# working.net
KiCad netlist of a schematic drawn in EAGLE
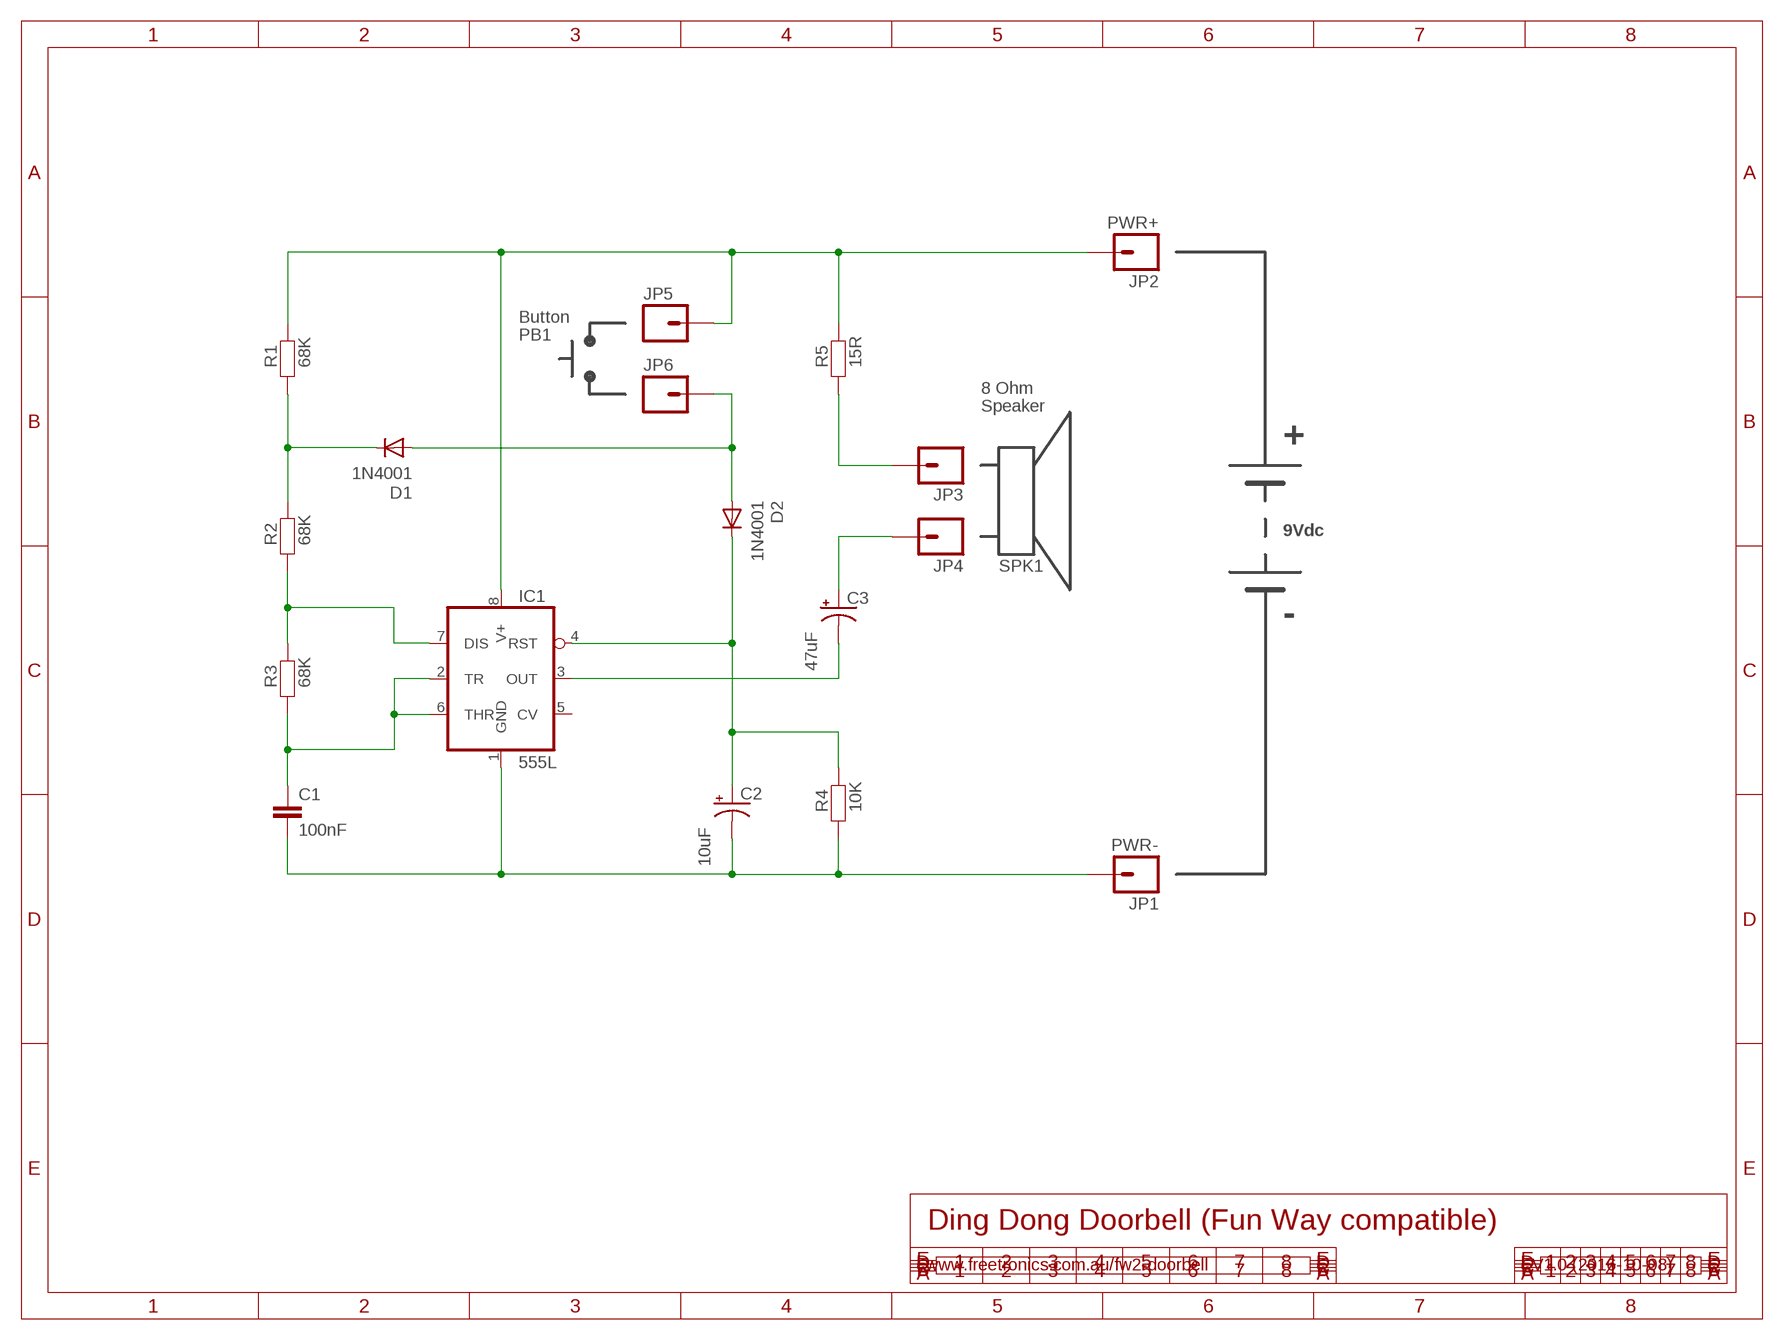
[diagram p0: schematic, sheet 1]

(export (version "E")
  (design (tool "Eeschema 10.0.6"))
  (components
    (comp (ref "C1")
      (value "100nF")
      (footprint "eagle-import:CAP-PTH-SMALL")
      (libsource (lib "eagle-import") (part "CAPPTH"))
    )
    (comp (ref "C2")
      (value "10uF")
      (footprint "eagle-import:CPOL-RADIAL-10UF-25V")
      (libsource (lib "eagle-import") (part "CAP_POLPTH2"))
    )
    (comp (ref "C3")
      (value "47uF")
      (footprint "eagle-import:CPOL-RADIAL-10UF-25V")
      (libsource (lib "eagle-import") (part "CAP_POLPTH2"))
    )
    (comp (ref "D1")
      (value "1N4001")
      (footprint "eagle-import:DIODE-1N4001")
      (libsource (lib "eagle-import") (part "DIODEPTH"))
    )
    (comp (ref "D2")
      (value "1N4001")
      (footprint "eagle-import:DIODE-1N4001")
      (libsource (lib "eagle-import") (part "DIODEPTH"))
    )
    (comp (ref "IC1")
      (value "555L")
      (footprint "eagle-import:DIL08L")
      (libsource (lib "eagle-import") (part "555L"))
    )
    (comp (ref "JP1")
      (value "PWR-")
      (footprint "eagle-import:1X01")
      (libsource (lib "eagle-import") (part "M01PTH"))
    )
    (comp (ref "JP2")
      (value "PWR+")
      (footprint "eagle-import:1X01")
      (libsource (lib "eagle-import") (part "M01PTH"))
    )
    (comp (ref "JP3")
      (value "SPKR+")
      (footprint "eagle-import:1X01")
      (libsource (lib "eagle-import") (part "M01PTH"))
    )
    (comp (ref "JP4")
      (value "SPKR-")
      (footprint "eagle-import:1X01")
      (libsource (lib "eagle-import") (part "M01PTH"))
    )
    (comp (ref "JP5")
      (value "PWR-")
      (footprint "eagle-import:1X01")
      (libsource (lib "eagle-import") (part "M01PTH"))
    )
    (comp (ref "JP6")
      (value "PWR-")
      (footprint "eagle-import:1X01")
      (libsource (lib "eagle-import") (part "M01PTH"))
    )
    (comp (ref "R1")
      (value "68K")
      (footprint "eagle-import:AXIAL-0.4-LARGE")
      (libsource (lib "eagle-import") (part "FREETRONICS_RESISTORPTH3"))
    )
    (comp (ref "R2")
      (value "68K")
      (footprint "eagle-import:AXIAL-0.4-LARGE")
      (libsource (lib "eagle-import") (part "FREETRONICS_RESISTORPTH3"))
    )
    (comp (ref "R3")
      (value "68K")
      (footprint "eagle-import:AXIAL-0.4-LARGE")
      (libsource (lib "eagle-import") (part "FREETRONICS_RESISTORPTH3"))
    )
    (comp (ref "R4")
      (value "10K")
      (footprint "eagle-import:AXIAL-0.4-LARGE")
      (libsource (lib "eagle-import") (part "FREETRONICS_RESISTORPTH3"))
    )
    (comp (ref "R5")
      (value "15R")
      (footprint "eagle-import:AXIAL-0.4-LARGE")
      (libsource (lib "eagle-import") (part "FREETRONICS_RESISTORPTH3"))
    )
  )
  (nets
    (net (code "1") (name "Net-(C2-+)") (class "Default")
      (node (ref "C2") (pin "1") (pinfunction "+_1") (pintype "passive"))
      (node (ref "D2") (pin "C") (pinfunction "C_C") (pintype "passive"))
      (node (ref "IC1") (pin "4") (pinfunction "RST_4") (pintype "input"))
      (node (ref "R4") (pin "P$2") (pinfunction "2_P$2") (pintype "passive"))
    )
    (net (code "2") (name "Net-(C2--)") (class "Default")
      (node (ref "C1") (pin "2") (pinfunction "2_2") (pintype "passive"))
      (node (ref "C2") (pin "2") (pinfunction "-_2") (pintype "passive"))
      (node (ref "IC1") (pin "1") (pinfunction "GND_1") (pintype "power_in"))
      (node (ref "JP1") (pin "1") (pinfunction "1_1") (pintype "passive"))
      (node (ref "R4") (pin "P$1") (pinfunction "1_P$1") (pintype "passive"))
    )
    (net (code "3") (name "Net-(C3-+)") (class "Default")
      (node (ref "C3") (pin "1") (pinfunction "+_1") (pintype "passive"))
      (node (ref "JP4") (pin "1") (pinfunction "1_1") (pintype "passive"))
    )
    (net (code "4") (name "Net-(C3--)") (class "Default")
      (node (ref "C3") (pin "2") (pinfunction "-_2") (pintype "passive"))
      (node (ref "IC1") (pin "3") (pinfunction "OUT_3") (pintype "output"))
    )
    (net (code "5") (name "Net-(D1-PadA)") (class "Default")
      (node (ref "D1") (pin "A") (pinfunction "A_A") (pintype "passive"))
      (node (ref "D2") (pin "A") (pinfunction "A_A") (pintype "passive"))
      (node (ref "JP6") (pin "1") (pinfunction "1_1") (pintype "passive"))
    )
    (net (code "6") (name "Net-(IC1-DIS)") (class "Default")
      (node (ref "IC1") (pin "7") (pinfunction "DIS_7") (pintype "input"))
      (node (ref "R2") (pin "P$1") (pinfunction "1_P$1") (pintype "passive"))
      (node (ref "R3") (pin "P$2") (pinfunction "2_P$2") (pintype "passive"))
    )
    (net (code "7") (name "Net-(IC1-THR)") (class "Default")
      (node (ref "C1") (pin "1") (pinfunction "1_1") (pintype "passive"))
      (node (ref "IC1") (pin "2") (pinfunction "TR_2") (pintype "input"))
      (node (ref "IC1") (pin "6") (pinfunction "THR_6") (pintype "input"))
      (node (ref "R3") (pin "P$1") (pinfunction "1_P$1") (pintype "passive"))
    )
    (net (code "8") (name "Net-(IC1-V+)") (class "Default")
      (node (ref "IC1") (pin "8") (pinfunction "V+_8") (pintype "power_in"))
      (node (ref "JP2") (pin "1") (pinfunction "1_1") (pintype "passive"))
      (node (ref "JP5") (pin "1") (pinfunction "1_1") (pintype "passive"))
      (node (ref "R1") (pin "P$2") (pinfunction "2_P$2") (pintype "passive"))
      (node (ref "R5") (pin "P$2") (pinfunction "2_P$2") (pintype "passive"))
    )
    (net (code "9") (name "Net-(R1-1)") (class "Default")
      (node (ref "D1") (pin "C") (pinfunction "C_C") (pintype "passive"))
      (node (ref "R1") (pin "P$1") (pinfunction "1_P$1") (pintype "passive"))
      (node (ref "R2") (pin "P$2") (pinfunction "2_P$2") (pintype "passive"))
    )
    (net (code "10") (name "Net-(R5-1)") (class "Default")
      (node (ref "JP3") (pin "1") (pinfunction "1_1") (pintype "passive"))
      (node (ref "R5") (pin "P$1") (pinfunction "1_P$1") (pintype "passive"))
    )
    (net (code "11") (name "unconnected-(IC1-CV-Pad5)") (class "Default")
      (node (ref "IC1") (pin "5") (pinfunction "CV_5") (pintype "input"))
    )
  )
)
